# LTC6803.net
KiCad netlist of a schematic drawn in Altium Designer
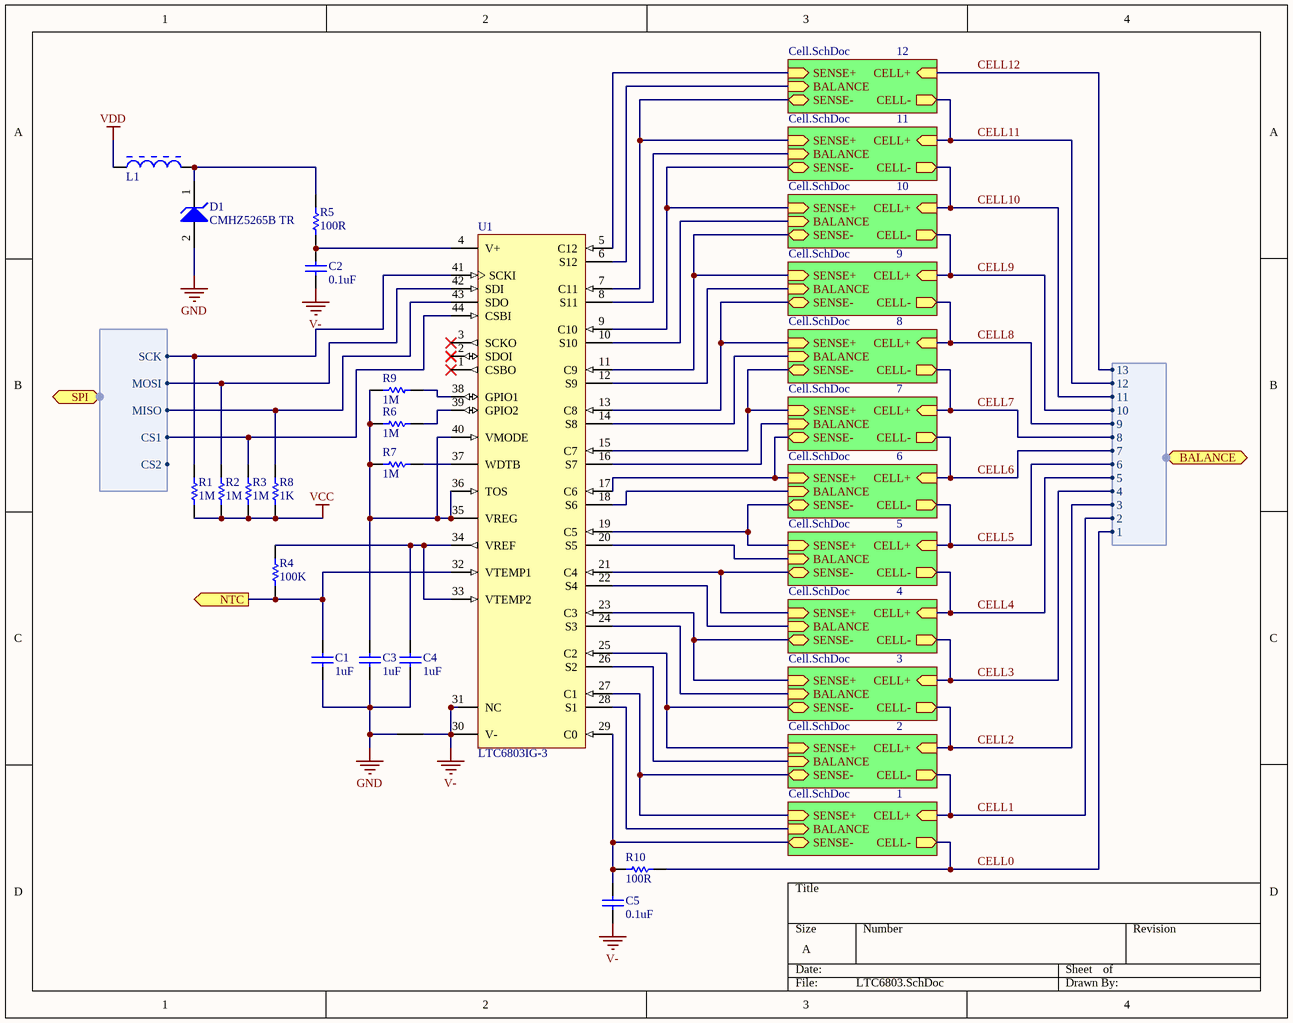
[diagram p0: LTC6803.SchDoc]

(export (version "E")
  (design (tool "Eeschema 10.0.6"))
  (components
    (comp (ref "*") (value "NetTie") (footprint "NetTie") (libsource (lib "Components") (part "NetTie")))
    (comp (ref "C1")
      (value "1uF")
      (footprint "C0402[1005X55]")
      (description "1uF 6.3V 10% 0402 (1005 Metric)")
      (fields (field (name "TOLERANCE") "10%") (field (name "PARTNUMBER") "GRM155R70J105KA12D"))
      (libsource (lib "Capacitors") (part "CAP_1uF_6.3V_0402_10%"))
    )
    (comp (ref "C2")
      (value "0.1uF")
      (footprint "C0402[1005X55]")
      (description "0.1uF 100V 10% 0402 (1005 Metric)")
      (fields (field (name "TOLERANCE") "10%") (field (name "PARTNUMBER") "GRM155R62A104KE14D"))
      (libsource (lib "Capacitors") (part "CAP_0.1uF_100V_0402_10%"))
    )
    (comp (ref "C3")
      (value "1uF")
      (footprint "C0402[1005X55]")
      (description "1uF 6.3V 10% 0402 (1005 Metric)")
      (fields (field (name "TOLERANCE") "10%") (field (name "PARTNUMBER") "GRM155R70J105KA12D"))
      (libsource (lib "Capacitors") (part "CAP_1uF_6.3V_0402_10%"))
    )
    (comp (ref "C4")
      (value "1uF")
      (footprint "C0402[1005X55]")
      (description "1uF 6.3V 10% 0402 (1005 Metric)")
      (fields (field (name "TOLERANCE") "10%") (field (name "PARTNUMBER") "GRM155R70J105KA12D"))
      (libsource (lib "Capacitors") (part "CAP_1uF_6.3V_0402_10%"))
    )
    (comp (ref "C5")
      (value "0.1uF")
      (footprint "C0402[1005X55]")
      (description "0.1uF 6.3V 10% 0402 (1005 Metric)")
      (fields (field (name "TOLERANCE") "10%") (field (name "PARTNUMBER") "GRM155R70J104KA01D"))
      (libsource (lib "Capacitors") (part "CAP_0.1uF_6.3V_0402_10%"))
    )
    (comp (ref "D1")
      (value "CMHZ5265B TR")
      (footprint "SOD-123")
      (description "Zener Diodes 500mW Zener Diode 185mA 58.9V to 2V")
      (fields (field (name "MANUFACTURER") "Central Semiconductor"))
      (libsource (lib "Diodes") (part "CMHZ5265B"))
    )
    (comp (ref "L1")
      (value "MURA-FB-2")
      (footprint "MURA-BLM31-B60-CHIP-2_V3")
      (description "EMI Filter Beads, Chips & Arrays 1206 33 OHM")
      (fields (field (name "PARTNUMBER") "BLM31PG330SN1L") (field (name "MANUFACTURER") "Murata"))
      (libsource (lib "Components") (part "MURA-FB-2"))
    )
    (comp (ref "R1")
      (value "1M")
      (footprint "R0402[1005]")
      (description "1M 0.063W 1% 0402 (1005 Metric)")
      (fields (field (name "POWER") "0.063W") (field (name "TOLERANCE") "1%"))
      (libsource (lib "Resistors") (part "RES_1M_0402_1%"))
    )
    (comp (ref "R2")
      (value "1M")
      (footprint "R0402[1005]")
      (description "1M 0.063W 1% 0402 (1005 Metric)")
      (fields (field (name "POWER") "0.063W") (field (name "TOLERANCE") "1%"))
      (libsource (lib "Resistors") (part "RES_1M_0402_1%"))
    )
    (comp (ref "R3")
      (value "1M")
      (footprint "R0402[1005]")
      (description "1M 0.063W 1% 0402 (1005 Metric)")
      (fields (field (name "POWER") "0.063W") (field (name "TOLERANCE") "1%"))
      (libsource (lib "Resistors") (part "RES_1M_0402_1%"))
    )
    (comp (ref "R4")
      (value "100K")
      (footprint "R0402[1005]")
      (description "100K 0.063W 1% 0402 (1005 Metric)")
      (fields (field (name "POWER") "0.063W") (field (name "TOLERANCE") "1%"))
      (libsource (lib "Resistors") (part "RES_100K_0402_1%"))
    )
    (comp (ref "R5")
      (value "100R")
      (footprint "R0402[1005]")
      (description "100R 0.063W 1% 0402 (1005 Metric)")
      (fields (field (name "POWER") "0.063W") (field (name "TOLERANCE") "1%"))
      (libsource (lib "Resistors") (part "RES_100R_0402_1%"))
    )
    (comp (ref "R6")
      (value "1M")
      (footprint "R0402[1005]")
      (description "1M 0.063W 1% 0402 (1005 Metric)")
      (fields (field (name "POWER") "0.063W") (field (name "TOLERANCE") "1%"))
      (libsource (lib "Resistors") (part "RES_1M_0402_1%"))
    )
    (comp (ref "R7")
      (value "1M")
      (footprint "R0402[1005]")
      (description "1M 0.063W 1% 0402 (1005 Metric)")
      (fields (field (name "POWER") "0.063W") (field (name "TOLERANCE") "1%"))
      (libsource (lib "Resistors") (part "RES_1M_0402_1%"))
    )
    (comp (ref "R8")
      (value "1K")
      (footprint "R0402[1005]")
      (description "1K 0.063W 1% 0402 (1005 Metric)")
      (fields (field (name "MANUFACTURER") "KOA Speer") (field (name "PARTNUMBER") "RK73H1ETTP1001F"))
      (libsource (lib "Resistors") (part "RES_1K_0402_1%"))
    )
    (comp (ref "R9")
      (value "1M")
      (footprint "R0402[1005]")
      (description "1M 0.063W 1% 0402 (1005 Metric)")
      (fields (field (name "POWER") "0.063W") (field (name "TOLERANCE") "1%"))
      (libsource (lib "Resistors") (part "RES_1M_0402_1%"))
    )
    (comp (ref "R10")
      (value "100R")
      (footprint "R0402[1005]")
      (description "100R 0.063W 1% 0402 (1005 Metric)")
      (fields (field (name "POWER") "0.063W") (field (name "TOLERANCE") "1%"))
      (libsource (lib "Resistors") (part "RES_100R_0402_1%"))
    )
    (comp (ref "U1")
      (value "LTC6803IG-3")
      (footprint "TSSOP-44")
      (fields (field (name "PARTNUMBER") "LTC6803IG-3#PBF") (field (name "MANUFACTURER") "Linear Technology"))
      (libsource (lib "ICs") (part "LTC6803IG-3"))
    )
  )
  (nets
    (net (code "3") (name "/BALANCE") (class "Default")
      (node (ref "U1") (pin "28") (pinfunction "S1_28") (pintype "tri_state"))
    )
    (net (code "4") (name "/BALANCE_1") (class "Default")
      (node (ref "U1") (pin "10") (pinfunction "S10_10") (pintype "tri_state"))
    )
    (net (code "5") (name "/BALANCE_2") (class "Default")
      (node (ref "U1") (pin "6") (pinfunction "S12_6") (pintype "tri_state"))
    )
    (net (code "6") (name "/BALANCE_3") (class "Default")
      (node (ref "U1") (pin "8") (pinfunction "S11_8") (pintype "tri_state"))
    )
    (net (code "7") (name "/BALANCE_4") (class "Default")
      (node (ref "U1") (pin "12") (pinfunction "S9_12") (pintype "tri_state"))
    )
    (net (code "8") (name "/BALANCE_5") (class "Default")
      (node (ref "U1") (pin "14") (pinfunction "S8_14") (pintype "tri_state"))
    )
    (net (code "9") (name "/BALANCE_6") (class "Default")
      (node (ref "U1") (pin "16") (pinfunction "S7_16") (pintype "tri_state"))
    )
    (net (code "10") (name "/BALANCE_7") (class "Default")
      (node (ref "U1") (pin "18") (pinfunction "S6_18") (pintype "tri_state"))
    )
    (net (code "11") (name "/BALANCE_8") (class "Default")
      (node (ref "U1") (pin "20") (pinfunction "S5_20") (pintype "tri_state"))
    )
    (net (code "12") (name "/BALANCE_9") (class "Default")
      (node (ref "U1") (pin "22") (pinfunction "S4_22") (pintype "tri_state"))
    )
    (net (code "13") (name "/BALANCE_10") (class "Default")
      (node (ref "U1") (pin "24") (pinfunction "S3_24") (pintype "tri_state"))
    )
    (net (code "14") (name "/BALANCE_11") (class "Default")
      (node (ref "U1") (pin "26") (pinfunction "S2_26") (pintype "tri_state"))
    )
    (net (code "15") (name "/CELL0") (class "Default")
      (node (ref "R10") (pin "2") (pinfunction "2_2") (pintype "passive"))
    )
    (net (code "28") (name "/NTC") (class "Default")
      (node (ref "C1") (pin "2") (pinfunction "2_2") (pintype "passive"))
      (node (ref "R4") (pin "1") (pinfunction "1_1") (pintype "passive"))
      (node (ref "U1") (pin "32") (pinfunction "VTEMP1_32") (pintype "input"))
    )
    (net (code "29") (name "/SENSE+") (class "Default")
      (node (ref "U1") (pin "27") (pinfunction "C1_27") (pintype "input"))
    )
    (net (code "30") (name "/SENSE+_1") (class "Default")
      (node (ref "U1") (pin "9") (pinfunction "C10_9") (pintype "input"))
    )
    (net (code "31") (name "/SENSE+_2") (class "Default")
      (node (ref "U1") (pin "11") (pinfunction "C9_11") (pintype "input"))
    )
    (net (code "32") (name "/SENSE+_3") (class "Default")
      (node (ref "U1") (pin "13") (pinfunction "C8_13") (pintype "input"))
    )
    (net (code "33") (name "/SENSE+_4") (class "Default")
      (node (ref "U1") (pin "7") (pinfunction "C11_7") (pintype "input"))
    )
    (net (code "34") (name "/SENSE+_5") (class "Default")
      (node (ref "U1") (pin "5") (pinfunction "C12_5") (pintype "input"))
    )
    (net (code "35") (name "/SENSE+_6") (class "Default")
      (node (ref "U1") (pin "15") (pinfunction "C7_15") (pintype "input"))
    )
    (net (code "36") (name "/SENSE+_7") (class "Default")
      (node (ref "U1") (pin "17") (pinfunction "C6_17") (pintype "input"))
    )
    (net (code "37") (name "/SENSE+_8") (class "Default")
      (node (ref "U1") (pin "19") (pinfunction "C5_19") (pintype "input"))
    )
    (net (code "38") (name "/SENSE+_9") (class "Default")
      (node (ref "U1") (pin "21") (pinfunction "C4_21") (pintype "input"))
    )
    (net (code "39") (name "/SENSE+_10") (class "Default")
      (node (ref "U1") (pin "23") (pinfunction "C3_23") (pintype "input"))
    )
    (net (code "40") (name "/SENSE+_11") (class "Default")
      (node (ref "U1") (pin "25") (pinfunction "C2_25") (pintype "input"))
    )
    (net (code "41") (name "/SENSE-") (class "Default")
      (node (ref "C5") (pin "2") (pinfunction "2_2") (pintype "passive"))
      (node (ref "R10") (pin "1") (pinfunction "1_1") (pintype "passive"))
      (node (ref "U1") (pin "29") (pinfunction "C0_29") (pintype "input"))
    )
    (net (code "44") (name "GND") (class "Default")
      (node (ref "*") (pin "1") (pinfunction "1_1") (pintype "passive"))
      (node (ref "C1") (pin "1") (pinfunction "1_1") (pintype "passive"))
      (node (ref "C3") (pin "1") (pinfunction "1_1") (pintype "passive"))
      (node (ref "C4") (pin "1") (pinfunction "1_1") (pintype "passive"))
      (node (ref "D1") (pin "2") (pinfunction "A_2") (pintype "passive"))
    )
    (net (code "45") (name "Net-(D1-K)") (class "Default")
      (node (ref "D1") (pin "1") (pinfunction "K_1") (pintype "passive"))
      (node (ref "L1") (pin "2") (pinfunction "2_2") (pintype "passive"))
      (node (ref "R5") (pin "2") (pinfunction "2_2") (pintype "passive"))
    )
    (net (code "46") (name "Net-(U1-CSBI)") (class "Default")
      (node (ref "R3") (pin "2") (pinfunction "2_2") (pintype "passive"))
      (node (ref "U1") (pin "44") (pinfunction "CSBI_44") (pintype "input"))
    )
    (net (code "47") (name "Net-(U1-GPIO1)") (class "Default")
      (node (ref "R9") (pin "1") (pinfunction "1_1") (pintype "passive"))
      (node (ref "U1") (pin "38") (pinfunction "GPIO1_38") (pintype "bidirectional"))
    )
    (net (code "48") (name "Net-(U1-GPIO2)") (class "Default")
      (node (ref "R6") (pin "1") (pinfunction "1_1") (pintype "passive"))
      (node (ref "U1") (pin "39") (pinfunction "GPIO2_39") (pintype "bidirectional"))
    )
    (net (code "49") (name "Net-(U1-SCKI)") (class "Default")
      (node (ref "R1") (pin "2") (pinfunction "2_2") (pintype "passive"))
      (node (ref "U1") (pin "41") (pinfunction "SCKI_41") (pintype "input"))
    )
    (net (code "50") (name "Net-(U1-SDI)") (class "Default")
      (node (ref "R2") (pin "2") (pinfunction "2_2") (pintype "passive"))
      (node (ref "U1") (pin "42") (pinfunction "SDI_42") (pintype "input"))
    )
    (net (code "51") (name "Net-(U1-SDO)") (class "Default")
      (node (ref "R8") (pin "1") (pinfunction "1_1") (pintype "passive"))
      (node (ref "U1") (pin "43") (pinfunction "SDO_43") (pintype "open_collector"))
    )
    (net (code "52") (name "Net-(U1-TOS)") (class "Default")
      (node (ref "C3") (pin "2") (pinfunction "2_2") (pintype "passive"))
      (node (ref "R6") (pin "2") (pinfunction "2_2") (pintype "passive"))
      (node (ref "R7") (pin "2") (pinfunction "2_2") (pintype "passive"))
      (node (ref "R9") (pin "2") (pinfunction "2_2") (pintype "passive"))
      (node (ref "U1") (pin "35") (pinfunction "VREG_35") (pintype "power_in"))
      (node (ref "U1") (pin "36") (pinfunction "TOS_36") (pintype "input"))
      (node (ref "U1") (pin "40") (pinfunction "VMODE_40") (pintype "input"))
    )
    (net (code "53") (name "Net-(U1-V+)") (class "Default")
      (node (ref "C2") (pin "2") (pinfunction "2_2") (pintype "passive"))
      (node (ref "R5") (pin "1") (pinfunction "1_1") (pintype "passive"))
      (node (ref "U1") (pin "4") (pinfunction "V+_4") (pintype "power_in"))
    )
    (net (code "54") (name "Net-(U1-VREF)") (class "Default")
      (node (ref "C4") (pin "2") (pinfunction "2_2") (pintype "passive"))
      (node (ref "R4") (pin "2") (pinfunction "2_2") (pintype "passive"))
      (node (ref "U1") (pin "33") (pinfunction "VTEMP2_33") (pintype "input"))
      (node (ref "U1") (pin "34") (pinfunction "VREF_34") (pintype "output"))
    )
    (net (code "55") (name "Net-(U1-WDTB)") (class "Default")
      (node (ref "R7") (pin "1") (pinfunction "1_1") (pintype "passive"))
      (node (ref "U1") (pin "37") (pinfunction "WDTB_37") (pintype "open_collector"))
    )
    (net (code "56") (name "V-") (class "Default")
      (node (ref "*") (pin "2") (pinfunction "2_2") (pintype "passive"))
      (node (ref "C2") (pin "1") (pinfunction "1_1") (pintype "passive"))
      (node (ref "C5") (pin "1") (pinfunction "1_1") (pintype "passive"))
      (node (ref "U1") (pin "30") (pinfunction "V-_30") (pintype "power_in"))
      (node (ref "U1") (pin "31") (pinfunction "NC_31") (pintype "passive"))
    )
    (net (code "57") (name "VCC") (class "Default")
      (node (ref "R1") (pin "1") (pinfunction "1_1") (pintype "passive"))
      (node (ref "R2") (pin "1") (pinfunction "1_1") (pintype "passive"))
      (node (ref "R3") (pin "1") (pinfunction "1_1") (pintype "passive"))
      (node (ref "R8") (pin "2") (pinfunction "2_2") (pintype "passive"))
    )
    (net (code "58") (name "VDD") (class "Default")
      (node (ref "L1") (pin "1") (pinfunction "1_1") (pintype "passive"))
    )
    (net (code "59") (name "unconnected-(U1-CSBO-Pad1)") (class "Default")
      (node (ref "U1") (pin "1") (pinfunction "CSBO_1") (pintype "output+no_connect"))
    )
    (net (code "60") (name "unconnected-(U1-SCKO-Pad3)") (class "Default")
      (node (ref "U1") (pin "3") (pinfunction "SCKO_3") (pintype "output+no_connect"))
    )
    (net (code "61") (name "unconnected-(U1-SDOI-Pad2)") (class "Default")
      (node (ref "U1") (pin "2") (pinfunction "SDOI_2") (pintype "bidirectional+no_connect"))
    )
  )
)
